# mainBoard.net
KiCad netlist of a schematic drawn in EAGLE
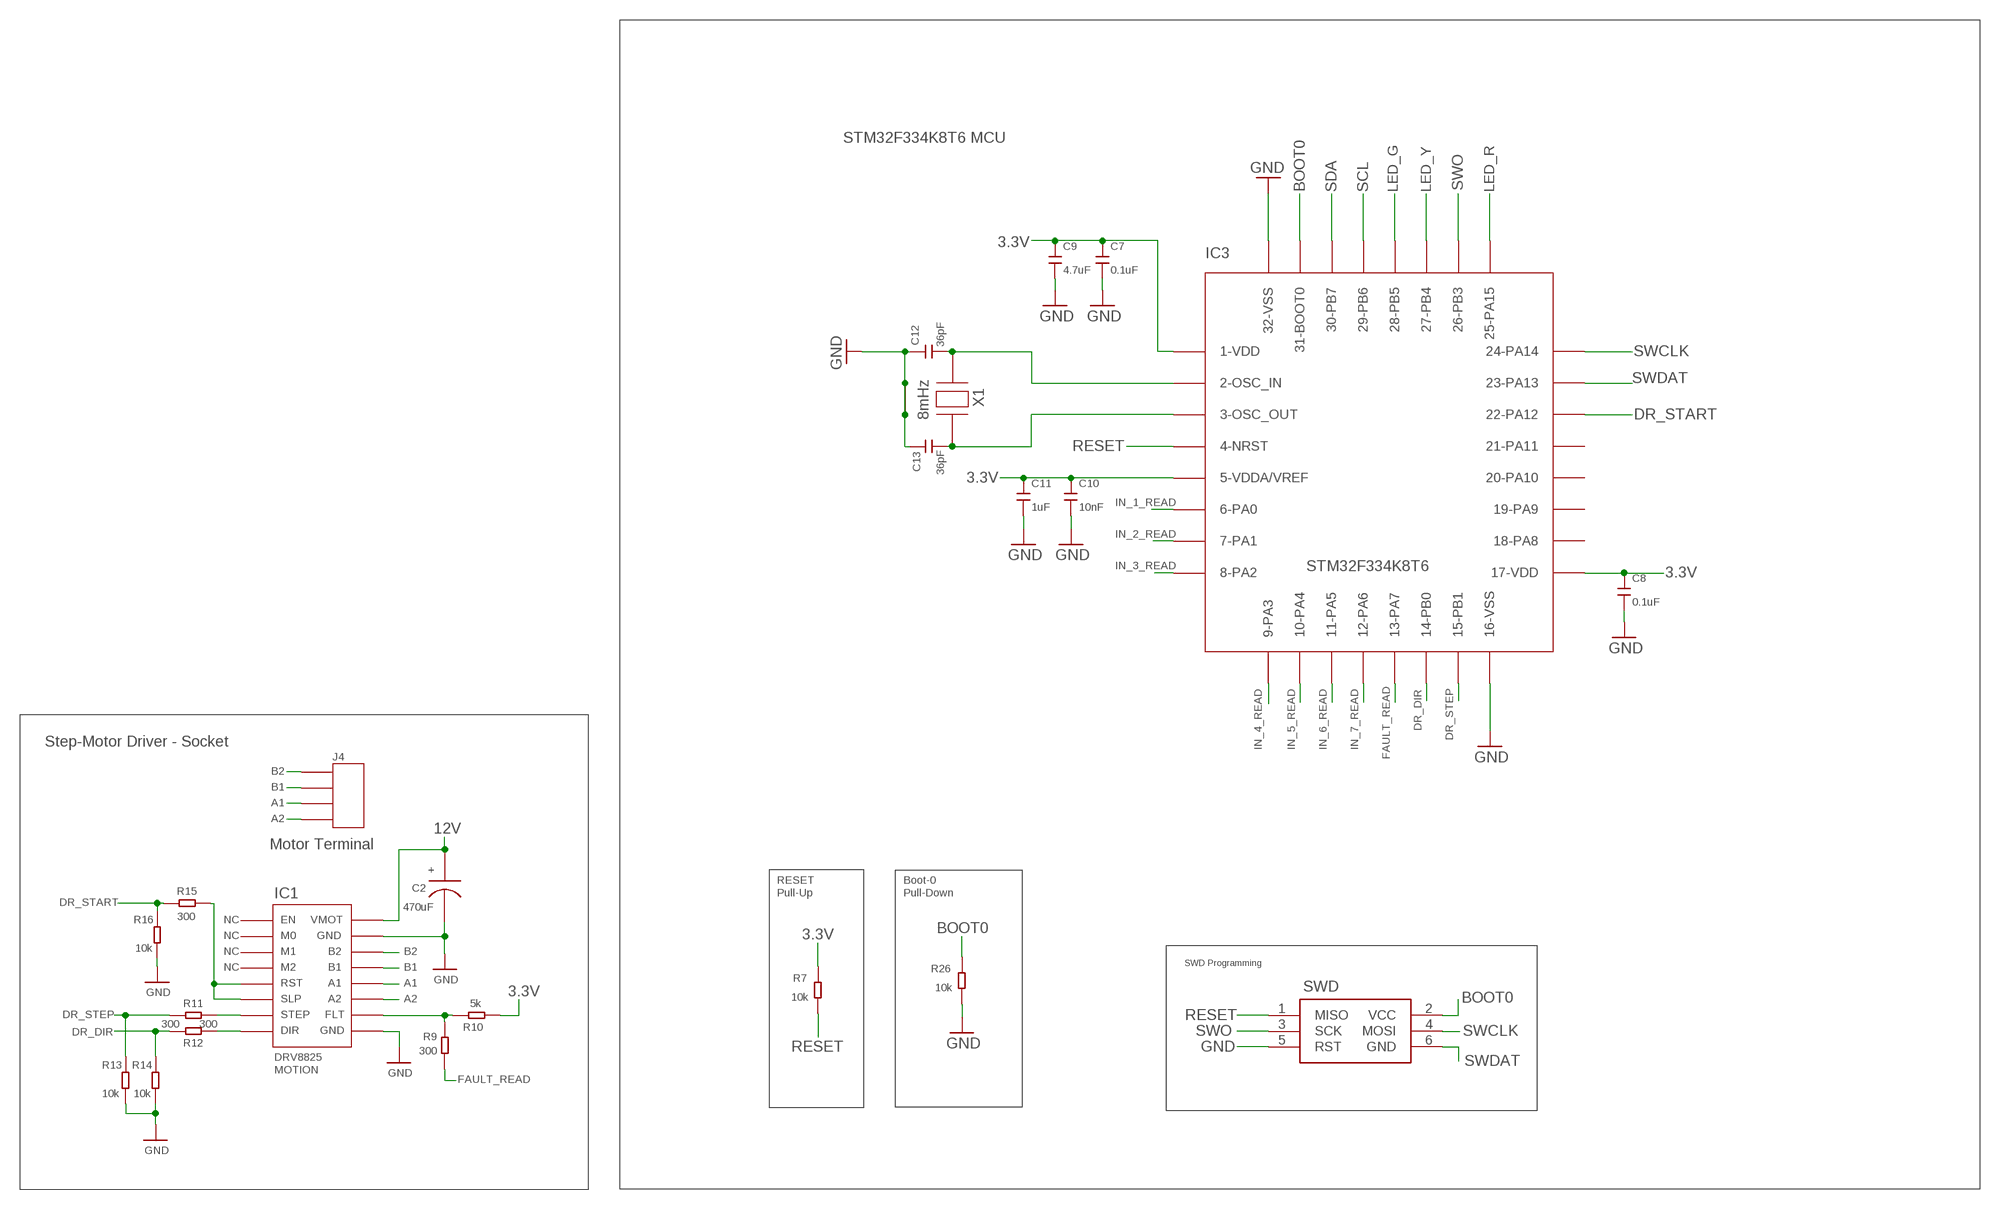
[diagram p0: schematic, sheet 1, part 1 of 2]
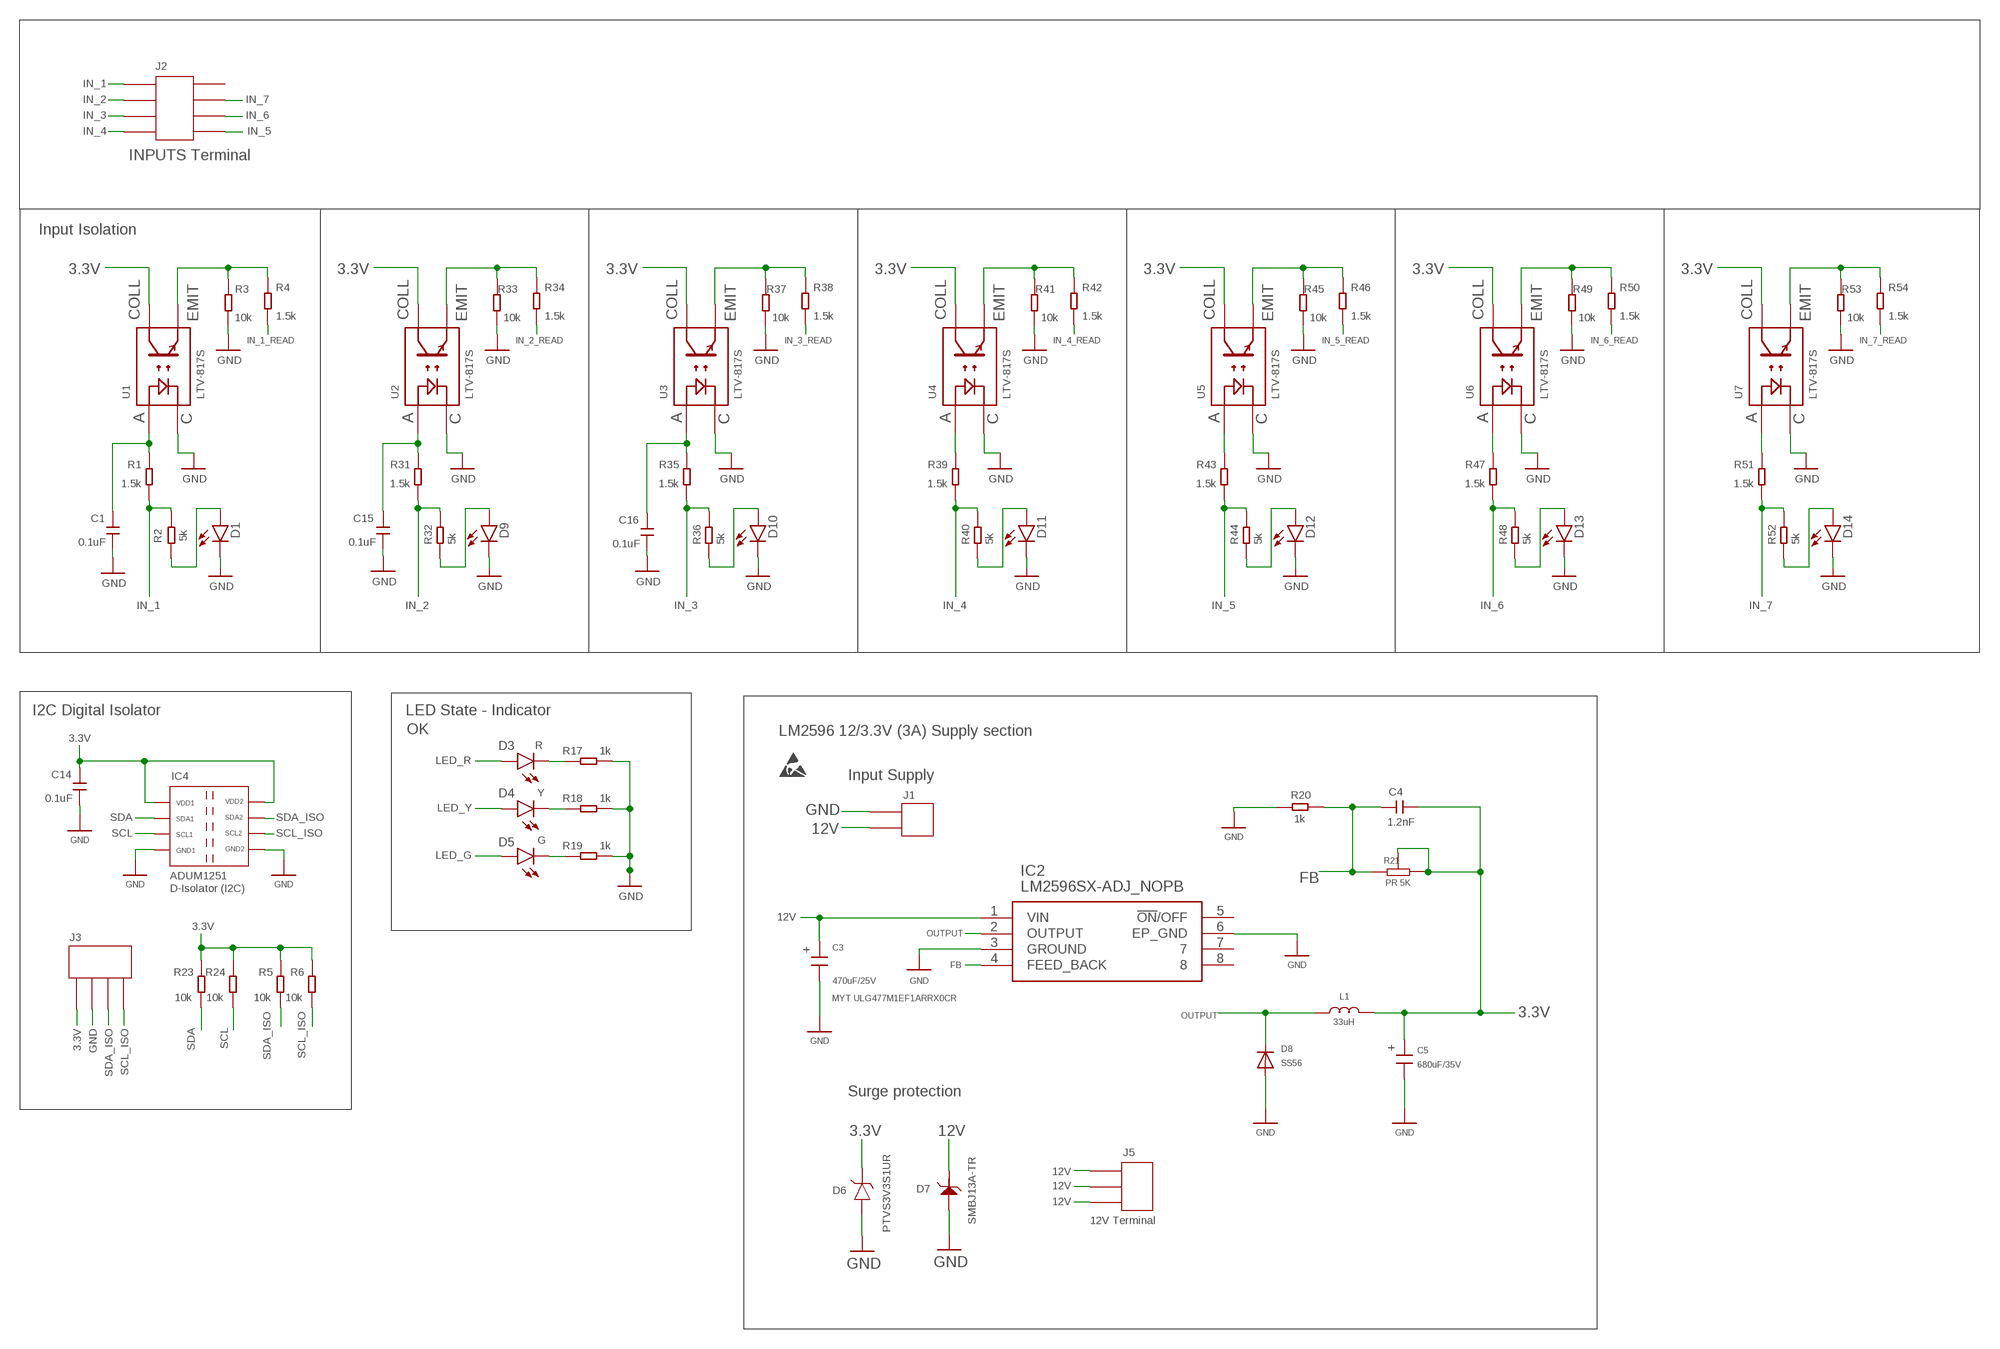
[diagram p1: schematic, sheet 1, part 2 of 2]

(export (version "E")
  (design (tool "Eeschema 10.0.6"))
  (components
    (comp (ref "C1")
      (value "0.1uF")
      (footprint "eagle-import:SMD-CAP-0805")
      (libsource (lib "eagle-import") (part "SMD-CAP-0805"))
    )
    (comp (ref "C2")
      (value "470uF")
      (footprint "eagle-import:EPCOS-CAP-10X16")
      (libsource (lib "eagle-import") (part "EPCOS-CAP-10X16"))
    )
    (comp (ref "C3")
      (value "MYT-680UF-25V-D8MM-F16")
      (footprint "eagle-import:MYT-680UF-25V-D8MM-F16")
      (libsource (lib "eagle-import") (part "MYT-680UF-25V-D8MM-F16"))
    )
    (comp (ref "C4")
      (value "1.2nF")
      (footprint "eagle-import:SMD-CAP-0805")
      (libsource (lib "eagle-import") (part "SMD-CAP-0805"))
    )
    (comp (ref "C5")
      (value "PANASONIC-SMT-CAP-680UF")
      (footprint "eagle-import:PANASONIC-SMT-CAP-680UF")
      (libsource (lib "eagle-import") (part "PANASONIC-SMT-CAP-680UF"))
    )
    (comp (ref "C7")
      (value "0.1uF")
      (footprint "eagle-import:SMD-CAP-0805")
      (libsource (lib "eagle-import") (part "SMD-CAP-0805"))
    )
    (comp (ref "C8")
      (value "0.1uF")
      (footprint "eagle-import:SMD-CAP-0805")
      (libsource (lib "eagle-import") (part "SMD-CAP-0805"))
    )
    (comp (ref "C9")
      (value "4.7uF")
      (footprint "eagle-import:SMD-CAP-0805")
      (libsource (lib "eagle-import") (part "SMD-CAP-0805"))
    )
    (comp (ref "C10")
      (value "10nF")
      (footprint "eagle-import:SMD-CAP-0805")
      (libsource (lib "eagle-import") (part "SMD-CAP-0805"))
    )
    (comp (ref "C11")
      (value "1uF")
      (footprint "eagle-import:SMD-CAP-0805")
      (libsource (lib "eagle-import") (part "SMD-CAP-0805"))
    )
    (comp (ref "C12")
      (value "36pF")
      (footprint "eagle-import:SMD-CAP-0603")
      (libsource (lib "eagle-import") (part "SMD-CAP-0603"))
    )
    (comp (ref "C13")
      (value "36pF")
      (footprint "eagle-import:SMD-CAP-0603")
      (libsource (lib "eagle-import") (part "SMD-CAP-0603"))
    )
    (comp (ref "C14")
      (value "0.1uF")
      (footprint "eagle-import:SMD-CAP-0805")
      (libsource (lib "eagle-import") (part "SMD-CAP-0805"))
    )
    (comp (ref "C15")
      (value "0.1uF")
      (footprint "eagle-import:SMD-CAP-0805")
      (libsource (lib "eagle-import") (part "SMD-CAP-0805"))
    )
    (comp (ref "C16")
      (value "0.1uF")
      (footprint "eagle-import:SMD-CAP-0805")
      (libsource (lib "eagle-import") (part "SMD-CAP-0805"))
    )
    (comp (ref "D1")
      (value "LED0603")
      (footprint "eagle-import:LED-0603")
      (libsource (lib "eagle-import") (part "LED0603"))
    )
    (comp (ref "D3")
      (value "R")
      (footprint "eagle-import:LED-0603")
      (libsource (lib "eagle-import") (part "LED0603"))
    )
    (comp (ref "D4")
      (value "Y")
      (footprint "eagle-import:LED-0603")
      (libsource (lib "eagle-import") (part "LED0603"))
    )
    (comp (ref "D5")
      (value "G")
      (footprint "eagle-import:LED-0603")
      (libsource (lib "eagle-import") (part "LED0603"))
    )
    (comp (ref "D6")
      (value "PTVS3V3S1UR")
      (footprint "eagle-import:PTVS3V3S1UR")
      (libsource (lib "eagle-import") (part "PTVS3V3S1UR"))
    )
    (comp (ref "D7")
      (value "TVS-SMBJ13A-LFUSE")
      (footprint "eagle-import:TVS-SMBJ13A-LFUSE")
      (libsource (lib "eagle-import") (part "TVS-SMBJ13A-LFUSE"))
    )
    (comp (ref "D8")
      (value "S2A")
      (footprint "eagle-import:DO214AA")
      (fields (field (name "MF") "Fairchild"))
      (libsource (lib "eagle-import") (part "S2A"))
    )
    (comp (ref "D9")
      (value "LED0603")
      (footprint "eagle-import:LED-0603")
      (libsource (lib "eagle-import") (part "LED0603"))
    )
    (comp (ref "D10")
      (value "LED0603")
      (footprint "eagle-import:LED-0603")
      (libsource (lib "eagle-import") (part "LED0603"))
    )
    (comp (ref "D11")
      (value "LED0603")
      (footprint "eagle-import:LED-0603")
      (libsource (lib "eagle-import") (part "LED0603"))
    )
    (comp (ref "D12")
      (value "LED0603")
      (footprint "eagle-import:LED-0603")
      (libsource (lib "eagle-import") (part "LED0603"))
    )
    (comp (ref "D13")
      (value "LED0603")
      (footprint "eagle-import:LED-0603")
      (libsource (lib "eagle-import") (part "LED0603"))
    )
    (comp (ref "D14")
      (value "LED0603")
      (footprint "eagle-import:LED-0603")
      (libsource (lib "eagle-import") (part "LED0603"))
    )
    (comp (ref "IC1")
      (value "DRV8825-DRIVER")
      (footprint "eagle-import:DRV8825-DRIVER")
      (libsource (lib "eagle-import") (part "DRV8825-DRIVER"))
    )
    (comp (ref "IC2")
      (value "LM2596SX-ADJ_NOPB")
      (footprint "eagle-import:LM2596SXADJNOPB")
      (fields
        (field (name "MANUFACTURER_PART_NUMBER") "LM2596SX-ADJ/NOPB")
        (field (name "MOUSER_PART_NUMBER") "926-LM2596SX-ADJNOPB")
      )
      (libsource (lib "eagle-import") (part "LM2596SX-ADJ_NOPB"))
    )
    (comp (ref "IC3")
      (value "STM32F334K8T6")
      (footprint "eagle-import:QFP80P900X900X160-32N")
      (libsource (lib "eagle-import") (part "STM32F334K8T6"))
    )
    (comp (ref "IC4")
      (value "ADUM1251ARZ-RL7")
      (footprint "eagle-import:ADUM1251ARZ-RL7")
      (libsource (lib "eagle-import") (part "ADUM1251ARZ-RL7"))
    )
    (comp (ref "J1")
      (value "DG127-5.0-2P")
      (footprint "eagle-import:DG127-5.0-2P")
      (libsource (lib "eagle-import") (part "DG127-5.0-2P"))
    )
    (comp (ref "J2")
      (value "5EHDR-08P-5.00")
      (footprint "eagle-import:5EHDR-08P-5.00")
      (libsource (lib "eagle-import") (part "5EHDR-08P-5.00"))
    )
    (comp (ref "J3")
      (value "DG127-5.0-4P")
      (footprint "eagle-import:DG127-5.0-4P")
      (libsource (lib "eagle-import") (part "DG127-5.0-4P"))
    )
    (comp (ref "J4")
      (value "DG127-5.0-4P")
      (footprint "eagle-import:DG127-5.0-4P")
      (libsource (lib "eagle-import") (part "DG127-5.0-4P"))
    )
    (comp (ref "J5")
      (value "PRESS-TERMINAL-5.0-3P")
      (footprint "eagle-import:PRESS-TERMINAL-5.0-3P")
      (libsource (lib "eagle-import") (part "PRESS-TERMINAL-5.0-3P"))
    )
    (comp (ref "L1")
      (value "SUNLTECHTEC-HSLO1365H330MTT")
      (footprint "eagle-import:SUNLTECHTEC-HSLO1365H330MTT")
      (libsource (lib "eagle-import") (part "SUNLTECHTEC-HSLO1365H330MTT"))
    )
    (comp (ref "R1")
      (value "1.5k")
      (footprint "eagle-import:R0805")
      (fields (field (name "MPN") "RL0805JR-070R1L"))
      (libsource (lib "eagle-import") (part "SMD-RES-0805"))
    )
    (comp (ref "R2")
      (value "5k")
      (footprint "eagle-import:SMD-RES-0603")
      (libsource (lib "eagle-import") (part "SMD-RES-0603"))
    )
    (comp (ref "R3")
      (value "10k")
      (footprint "eagle-import:R0805")
      (fields (field (name "MPN") "RL0805JR-070R1L"))
      (libsource (lib "eagle-import") (part "SMD-RES-0805"))
    )
    (comp (ref "R4")
      (value "1.5k")
      (footprint "eagle-import:R0805")
      (fields (field (name "MPN") "RL0805JR-070R1L"))
      (libsource (lib "eagle-import") (part "SMD-RES-0805"))
    )
    (comp (ref "R5")
      (value "10k")
      (footprint "eagle-import:R0805")
      (fields (field (name "MPN") "RL0805JR-070R1L"))
      (libsource (lib "eagle-import") (part "SMD-RES-0805"))
    )
    (comp (ref "R6")
      (value "10k")
      (footprint "eagle-import:R0805")
      (fields (field (name "MPN") "RL0805JR-070R1L"))
      (libsource (lib "eagle-import") (part "SMD-RES-0805"))
    )
    (comp (ref "R7")
      (value "10k")
      (footprint "eagle-import:SMD-RES-0603")
      (libsource (lib "eagle-import") (part "SMD-RES-0603"))
    )
    (comp (ref "R9")
      (value "300")
      (footprint "eagle-import:R0805")
      (fields (field (name "MPN") "RL0805JR-070R1L"))
      (libsource (lib "eagle-import") (part "SMD-RES-0805"))
    )
    (comp (ref "R10")
      (value "5k")
      (footprint "eagle-import:R0805")
      (fields (field (name "MPN") "RL0805JR-070R1L"))
      (libsource (lib "eagle-import") (part "SMD-RES-0805"))
    )
    (comp (ref "R11")
      (value "300")
      (footprint "eagle-import:R0805")
      (fields (field (name "MPN") "RL0805JR-070R1L"))
      (libsource (lib "eagle-import") (part "SMD-RES-0805"))
    )
    (comp (ref "R12")
      (value "300")
      (footprint "eagle-import:R0805")
      (fields (field (name "MPN") "RL0805JR-070R1L"))
      (libsource (lib "eagle-import") (part "SMD-RES-0805"))
    )
    (comp (ref "R13")
      (value "10k")
      (footprint "eagle-import:R0805")
      (fields (field (name "MPN") "RL0805JR-070R1L"))
      (libsource (lib "eagle-import") (part "SMD-RES-0805"))
    )
    (comp (ref "R14")
      (value "10k")
      (footprint "eagle-import:R0805")
      (fields (field (name "MPN") "RL0805JR-070R1L"))
      (libsource (lib "eagle-import") (part "SMD-RES-0805"))
    )
    (comp (ref "R15")
      (value "300")
      (footprint "eagle-import:R0805")
      (fields (field (name "MPN") "RL0805JR-070R1L"))
      (libsource (lib "eagle-import") (part "SMD-RES-0805"))
    )
    (comp (ref "R16")
      (value "10k")
      (footprint "eagle-import:R0805")
      (fields (field (name "MPN") "RL0805JR-070R1L"))
      (libsource (lib "eagle-import") (part "SMD-RES-0805"))
    )
    (comp (ref "R17")
      (value "1k")
      (footprint "eagle-import:SMD-RES-0603")
      (libsource (lib "eagle-import") (part "SMD-RES-0603"))
    )
    (comp (ref "R18")
      (value "1k")
      (footprint "eagle-import:SMD-RES-0603")
      (libsource (lib "eagle-import") (part "SMD-RES-0603"))
    )
    (comp (ref "R19")
      (value "1k")
      (footprint "eagle-import:SMD-RES-0603")
      (libsource (lib "eagle-import") (part "SMD-RES-0603"))
    )
    (comp (ref "R20")
      (value "1k")
      (footprint "eagle-import:R0805")
      (fields (field (name "MPN") "RL0805JR-070R1L"))
      (libsource (lib "eagle-import") (part "SMD-RES-0805"))
    )
    (comp (ref "R21")
      (value "BOURNS-3296W-PREC-RESISTOR-5K")
      (footprint "eagle-import:BOURNS-3296W-PREC-RESISTOR-5K")
      (libsource (lib "eagle-import") (part "BOURNS-3296W-PREC-RESISTOR-5K"))
    )
    (comp (ref "R23")
      (value "10k")
      (footprint "eagle-import:R0805")
      (fields (field (name "MPN") "RL0805JR-070R1L"))
      (libsource (lib "eagle-import") (part "SMD-RES-0805"))
    )
    (comp (ref "R24")
      (value "10k")
      (footprint "eagle-import:R0805")
      (fields (field (name "MPN") "RL0805JR-070R1L"))
      (libsource (lib "eagle-import") (part "SMD-RES-0805"))
    )
    (comp (ref "R26")
      (value "10k")
      (footprint "eagle-import:SMD-RES-0603")
      (libsource (lib "eagle-import") (part "SMD-RES-0603"))
    )
    (comp (ref "R31")
      (value "1.5k")
      (footprint "eagle-import:R0805")
      (fields (field (name "MPN") "RL0805JR-070R1L"))
      (libsource (lib "eagle-import") (part "SMD-RES-0805"))
    )
    (comp (ref "R32")
      (value "5k")
      (footprint "eagle-import:SMD-RES-0603")
      (libsource (lib "eagle-import") (part "SMD-RES-0603"))
    )
    (comp (ref "R33")
      (value "10k")
      (footprint "eagle-import:R0805")
      (fields (field (name "MPN") "RL0805JR-070R1L"))
      (libsource (lib "eagle-import") (part "SMD-RES-0805"))
    )
    (comp (ref "R34")
      (value "1.5k")
      (footprint "eagle-import:R0805")
      (fields (field (name "MPN") "RL0805JR-070R1L"))
      (libsource (lib "eagle-import") (part "SMD-RES-0805"))
    )
    (comp (ref "R35")
      (value "1.5k")
      (footprint "eagle-import:R0805")
      (fields (field (name "MPN") "RL0805JR-070R1L"))
      (libsource (lib "eagle-import") (part "SMD-RES-0805"))
    )
    (comp (ref "R36")
      (value "5k")
      (footprint "eagle-import:SMD-RES-0603")
      (libsource (lib "eagle-import") (part "SMD-RES-0603"))
    )
    (comp (ref "R37")
      (value "10k")
      (footprint "eagle-import:R0805")
      (fields (field (name "MPN") "RL0805JR-070R1L"))
      (libsource (lib "eagle-import") (part "SMD-RES-0805"))
    )
    (comp (ref "R38")
      (value "1.5k")
      (footprint "eagle-import:R0805")
      (fields (field (name "MPN") "RL0805JR-070R1L"))
      (libsource (lib "eagle-import") (part "SMD-RES-0805"))
    )
    (comp (ref "R39")
      (value "1.5k")
      (footprint "eagle-import:R0805")
      (fields (field (name "MPN") "RL0805JR-070R1L"))
      (libsource (lib "eagle-import") (part "SMD-RES-0805"))
    )
    (comp (ref "R40")
      (value "5k")
      (footprint "eagle-import:SMD-RES-0603")
      (libsource (lib "eagle-import") (part "SMD-RES-0603"))
    )
    (comp (ref "R41")
      (value "10k")
      (footprint "eagle-import:R0805")
      (fields (field (name "MPN") "RL0805JR-070R1L"))
      (libsource (lib "eagle-import") (part "SMD-RES-0805"))
    )
    (comp (ref "R42")
      (value "1.5k")
      (footprint "eagle-import:R0805")
      (fields (field (name "MPN") "RL0805JR-070R1L"))
      (libsource (lib "eagle-import") (part "SMD-RES-0805"))
    )
    (comp (ref "R43")
      (value "1.5k")
      (footprint "eagle-import:R0805")
      (fields (field (name "MPN") "RL0805JR-070R1L"))
      (libsource (lib "eagle-import") (part "SMD-RES-0805"))
    )
    (comp (ref "R44")
      (value "5k")
      (footprint "eagle-import:SMD-RES-0603")
      (libsource (lib "eagle-import") (part "SMD-RES-0603"))
    )
    (comp (ref "R45")
      (value "10k")
      (footprint "eagle-import:R0805")
      (fields (field (name "MPN") "RL0805JR-070R1L"))
      (libsource (lib "eagle-import") (part "SMD-RES-0805"))
    )
    (comp (ref "R46")
      (value "1.5k")
      (footprint "eagle-import:R0805")
      (fields (field (name "MPN") "RL0805JR-070R1L"))
      (libsource (lib "eagle-import") (part "SMD-RES-0805"))
    )
    (comp (ref "R47")
      (value "1.5k")
      (footprint "eagle-import:R0805")
      (fields (field (name "MPN") "RL0805JR-070R1L"))
      (libsource (lib "eagle-import") (part "SMD-RES-0805"))
    )
    (comp (ref "R48")
      (value "5k")
      (footprint "eagle-import:SMD-RES-0603")
      (libsource (lib "eagle-import") (part "SMD-RES-0603"))
    )
    (comp (ref "R49")
      (value "10k")
      (footprint "eagle-import:R0805")
      (fields (field (name "MPN") "RL0805JR-070R1L"))
      (libsource (lib "eagle-import") (part "SMD-RES-0805"))
    )
    (comp (ref "R50")
      (value "1.5k")
      (footprint "eagle-import:R0805")
      (fields (field (name "MPN") "RL0805JR-070R1L"))
      (libsource (lib "eagle-import") (part "SMD-RES-0805"))
    )
    (comp (ref "R51")
      (value "1.5k")
      (footprint "eagle-import:R0805")
      (fields (field (name "MPN") "RL0805JR-070R1L"))
      (libsource (lib "eagle-import") (part "SMD-RES-0805"))
    )
    (comp (ref "R52")
      (value "5k")
      (footprint "eagle-import:SMD-RES-0603")
      (libsource (lib "eagle-import") (part "SMD-RES-0603"))
    )
    (comp (ref "R53")
      (value "10k")
      (footprint "eagle-import:R0805")
      (fields (field (name "MPN") "RL0805JR-070R1L"))
      (libsource (lib "eagle-import") (part "SMD-RES-0805"))
    )
    (comp (ref "R54")
      (value "1.5k")
      (footprint "eagle-import:R0805")
      (fields (field (name "MPN") "RL0805JR-070R1L"))
      (libsource (lib "eagle-import") (part "SMD-RES-0805"))
    )
    (comp (ref "SWD")
      (value "AVRISP-6")
      (footprint "eagle-import:AVRISP")
      (libsource (lib "eagle-import") (part "AVRISP-6"))
    )
    (comp (ref "U$1")
      (value "ESD-LOGO")
      (footprint "eagle-import:ESD-LOGO")
      (libsource (lib "eagle-import") (part "ESD-LOGO"))
    )
    (comp (ref "U1")
      (value "LTV-817S")
      (footprint "eagle-import:LTV-817S")
      (libsource (lib "eagle-import") (part "LTV-817S"))
    )
    (comp (ref "U2")
      (value "LTV-817S")
      (footprint "eagle-import:LTV-817S")
      (libsource (lib "eagle-import") (part "LTV-817S"))
    )
    (comp (ref "U3")
      (value "LTV-817S")
      (footprint "eagle-import:LTV-817S")
      (libsource (lib "eagle-import") (part "LTV-817S"))
    )
    (comp (ref "U4")
      (value "LTV-817S")
      (footprint "eagle-import:LTV-817S")
      (libsource (lib "eagle-import") (part "LTV-817S"))
    )
    (comp (ref "U5")
      (value "LTV-817S")
      (footprint "eagle-import:LTV-817S")
      (libsource (lib "eagle-import") (part "LTV-817S"))
    )
    (comp (ref "U6")
      (value "LTV-817S")
      (footprint "eagle-import:LTV-817S")
      (libsource (lib "eagle-import") (part "LTV-817S"))
    )
    (comp (ref "U7")
      (value "LTV-817S")
      (footprint "eagle-import:LTV-817S")
      (libsource (lib "eagle-import") (part "LTV-817S"))
    )
    (comp (ref "X1")
      (value "8mHz")
      (footprint "eagle-import:CRYSTALL-YTC-X50328MSB4SI")
      (libsource (lib "eagle-import") (part "CRYSTALL-YTC-X50328MSB4SI"))
    )
  )
  (nets
    (net (code "1") (name "/3.3V") (class "Default")
      (node (ref "C10") (pin "2") (pinfunction "2_2") (pintype "passive"))
      (node (ref "C11") (pin "2") (pinfunction "2_2") (pintype "passive"))
      (node (ref "C14") (pin "2") (pinfunction "2_2") (pintype "passive"))
      (node (ref "C4") (pin "2") (pinfunction "2_2") (pintype "passive"))
      (node (ref "C5") (pin "+") (pinfunction "+_+") (pintype "bidirectional"))
      (node (ref "C7") (pin "2") (pinfunction "2_2") (pintype "passive"))
      (node (ref "C8") (pin "2") (pinfunction "2_2") (pintype "passive"))
      (node (ref "C9") (pin "2") (pinfunction "2_2") (pintype "passive"))
      (node (ref "D6") (pin "C") (pinfunction "C_C") (pintype "bidirectional"))
      (node (ref "IC3") (pin "1-VDD") (pinfunction "1-VDD_1-VDD") (pintype "bidirectional"))
      (node (ref "IC3") (pin "17-VDD") (pinfunction "17-VDD_17-VDD") (pintype "bidirectional"))
      (node (ref "IC3") (pin "5-VDDA/VREF") (pinfunction "5-VDDA/VREF_5-VDDA/VREF") (pintype "bidirectional"))
      (node (ref "IC4") (pin "VDD1") (pinfunction "VDD1_VDD1") (pintype "bidirectional"))
      (node (ref "IC4") (pin "VDD2") (pinfunction "VDD2_VDD2") (pintype "bidirectional"))
      (node (ref "J3") (pin "P$1") (pinfunction "P$1_P$1") (pintype "bidirectional"))
      (node (ref "L1") (pin "P$2") (pinfunction "P$2_P$2") (pintype "bidirectional"))
      (node (ref "R10") (pin "2") (pinfunction "2_2") (pintype "passive"))
      (node (ref "R21") (pin "CW-3") (pinfunction "CW-3_CW-3") (pintype "bidirectional"))
      (node (ref "R21") (pin "WIPER-2") (pinfunction "WIPER-2_WIPER-2") (pintype "bidirectional"))
      (node (ref "R23") (pin "2") (pinfunction "2_2") (pintype "passive"))
      (node (ref "R24") (pin "2") (pinfunction "2_2") (pintype "passive"))
      (node (ref "R5") (pin "2") (pinfunction "2_2") (pintype "passive"))
      (node (ref "R6") (pin "2") (pinfunction "2_2") (pintype "passive"))
      (node (ref "R7") (pin "2") (pinfunction "2_2") (pintype "passive"))
      (node (ref "U1") (pin "COLL") (pinfunction "COLLECTOR_COLL") (pintype "bidirectional"))
      (node (ref "U2") (pin "COLL") (pinfunction "COLLECTOR_COLL") (pintype "bidirectional"))
      (node (ref "U3") (pin "COLL") (pinfunction "COLLECTOR_COLL") (pintype "bidirectional"))
      (node (ref "U4") (pin "COLL") (pinfunction "COLLECTOR_COLL") (pintype "bidirectional"))
      (node (ref "U5") (pin "COLL") (pinfunction "COLLECTOR_COLL") (pintype "bidirectional"))
      (node (ref "U6") (pin "COLL") (pinfunction "COLLECTOR_COLL") (pintype "bidirectional"))
      (node (ref "U7") (pin "COLL") (pinfunction "COLLECTOR_COLL") (pintype "bidirectional"))
    )
    (net (code "2") (name "/12V") (class "Default")
      (node (ref "C2") (pin "+") (pinfunction "+_+") (pintype "bidirectional"))
      (node (ref "C3") (pin "+") (pinfunction "+_+") (pintype "bidirectional"))
      (node (ref "D7") (pin "-") (pinfunction "-_-") (pintype "bidirectional"))
      (node (ref "IC1") (pin "VMOT") (pinfunction "VMOT_VMOT") (pintype "bidirectional"))
      (node (ref "IC2") (pin "1") (pinfunction "VIN_1") (pintype "bidirectional"))
      (node (ref "J1") (pin "P$2") (pinfunction "P$2_P$2") (pintype "bidirectional"))
      (node (ref "J5") (pin "A1") (pinfunction "P$1_A1") (pintype "bidirectional"))
      (node (ref "J5") (pin "A2") (pinfunction "P$2_A2") (pintype "bidirectional"))
      (node (ref "J5") (pin "A3") (pinfunction "P$3_A3") (pintype "bidirectional"))
      (node (ref "J5") (pin "B1") (pinfunction "P$1_B1") (pintype "bidirectional"))
      (node (ref "J5") (pin "B2") (pinfunction "P$2_B2") (pintype "bidirectional"))
      (node (ref "J5") (pin "B3") (pinfunction "P$3_B3") (pintype "bidirectional"))
    )
    (net (code "3") (name "/A1") (class "Default")
      (node (ref "IC1") (pin "A1") (pinfunction "A1_A1") (pintype "bidirectional"))
      (node (ref "J4") (pin "P$3") (pinfunction "P$3_P$3") (pintype "bidirectional"))
    )
    (net (code "4") (name "/A2") (class "Default")
      (node (ref "IC1") (pin "A2") (pinfunction "A2_A2") (pintype "bidirectional"))
      (node (ref "J4") (pin "P$4") (pinfunction "P$4_P$4") (pintype "bidirectional"))
    )
    (net (code "5") (name "/B1") (class "Default")
      (node (ref "IC1") (pin "B1") (pinfunction "B1_B1") (pintype "bidirectional"))
      (node (ref "J4") (pin "P$2") (pinfunction "P$2_P$2") (pintype "bidirectional"))
    )
    (net (code "6") (name "/B2") (class "Default")
      (node (ref "IC1") (pin "B2") (pinfunction "B2_B2") (pintype "bidirectional"))
      (node (ref "J4") (pin "P$1") (pinfunction "P$1_P$1") (pintype "bidirectional"))
    )
    (net (code "7") (name "/BOOT0") (class "Default")
      (node (ref "IC3") (pin "31-BOOT0") (pinfunction "31-BOOT0_31-BOOT0") (pintype "bidirectional"))
      (node (ref "R26") (pin "2") (pinfunction "2_2") (pintype "passive"))
      (node (ref "SWD") (pin "2") (pinfunction "VCC_2") (pintype "power_in"))
    )
    (net (code "8") (name "/DR_DIR") (class "Default")
      (node (ref "IC3") (pin "14-PB0") (pinfunction "14-PB0_14-PB0") (pintype "bidirectional"))
      (node (ref "R12") (pin "1") (pinfunction "1_1") (pintype "passive"))
      (node (ref "R14") (pin "2") (pinfunction "2_2") (pintype "passive"))
    )
    (net (code "9") (name "/DR_START") (class "Default")
      (node (ref "IC3") (pin "22-PA12") (pinfunction "22-PA12_22-PA12") (pintype "bidirectional"))
      (node (ref "R15") (pin "1") (pinfunction "1_1") (pintype "passive"))
      (node (ref "R16") (pin "2") (pinfunction "2_2") (pintype "passive"))
    )
    (net (code "10") (name "/DR_STEP") (class "Default")
      (node (ref "IC3") (pin "15-PB1") (pinfunction "15-PB1_15-PB1") (pintype "bidirectional"))
      (node (ref "R11") (pin "1") (pinfunction "1_1") (pintype "passive"))
      (node (ref "R13") (pin "2") (pinfunction "2_2") (pintype "passive"))
    )
    (net (code "11") (name "/FAULT_READ") (class "Default")
      (node (ref "IC3") (pin "13-PA7") (pinfunction "13-PA7_13-PA7") (pintype "bidirectional"))
      (node (ref "R9") (pin "2") (pinfunction "2_2") (pintype "passive"))
    )
    (net (code "12") (name "/FB") (class "Default")
      (node (ref "C4") (pin "1") (pinfunction "1_1") (pintype "passive"))
      (node (ref "IC2") (pin "4") (pinfunction "FEED_BACK_4") (pintype "bidirectional"))
      (node (ref "R20") (pin "2") (pinfunction "2_2") (pintype "passive"))
      (node (ref "R21") (pin "CCW-1") (pinfunction "CCW-1_CCW-1") (pintype "bidirectional"))
    )
    (net (code "13") (name "/IN_1") (class "Default")
      (node (ref "J2") (pin "1") (pinfunction "1_1") (pintype "bidirectional"))
      (node (ref "R1") (pin "1") (pinfunction "1_1") (pintype "passive"))
      (node (ref "R2") (pin "2") (pinfunction "2_2") (pintype "passive"))
    )
    (net (code "14") (name "/IN_1_READ") (class "Default")
      (node (ref "IC3") (pin "6-PA0") (pinfunction "6-PA0_6-PA0") (pintype "bidirectional"))
      (node (ref "R4") (pin "2") (pinfunction "2_2") (pintype "passive"))
    )
    (net (code "15") (name "/IN_2") (class "Default")
      (node (ref "J2") (pin "2") (pinfunction "2_2") (pintype "bidirectional"))
      (node (ref "R31") (pin "1") (pinfunction "1_1") (pintype "passive"))
      (node (ref "R32") (pin "2") (pinfunction "2_2") (pintype "passive"))
    )
    (net (code "16") (name "/IN_2_READ") (class "Default")
      (node (ref "IC3") (pin "7-PA1") (pinfunction "7-PA1_7-PA1") (pintype "bidirectional"))
      (node (ref "R34") (pin "2") (pinfunction "2_2") (pintype "passive"))
    )
    (net (code "17") (name "/IN_3") (class "Default")
      (node (ref "J2") (pin "3") (pinfunction "3_3") (pintype "bidirectional"))
      (node (ref "R35") (pin "1") (pinfunction "1_1") (pintype "passive"))
      (node (ref "R36") (pin "2") (pinfunction "2_2") (pintype "passive"))
    )
    (net (code "18") (name "/IN_3_READ") (class "Default")
      (node (ref "IC3") (pin "8-PA2") (pinfunction "8-PA2_8-PA2") (pintype "bidirectional"))
      (node (ref "R38") (pin "2") (pinfunction "2_2") (pintype "passive"))
    )
    (net (code "19") (name "/IN_4") (class "Default")
      (node (ref "J2") (pin "4") (pinfunction "4_4") (pintype "bidirectional"))
      (node (ref "R39") (pin "1") (pinfunction "1_1") (pintype "passive"))
      (node (ref "R40") (pin "2") (pinfunction "2_2") (pintype "passive"))
    )
    (net (code "20") (name "/IN_4_READ") (class "Default")
      (node (ref "IC3") (pin "9-PA3") (pinfunction "9-PA3_9-PA3") (pintype "bidirectional"))
      (node (ref "R42") (pin "2") (pinfunction "2_2") (pintype "passive"))
    )
    (net (code "21") (name "/IN_5") (class "Default")
      (node (ref "J2") (pin "5") (pinfunction "5_5") (pintype "bidirectional"))
      (node (ref "R43") (pin "1") (pinfunction "1_1") (pintype "passive"))
      (node (ref "R44") (pin "2") (pinfunction "2_2") (pintype "passive"))
    )
    (net (code "22") (name "/IN_5_READ") (class "Default")
      (node (ref "IC3") (pin "10-PA4") (pinfunction "10-PA4_10-PA4") (pintype "bidirectional"))
      (node (ref "R46") (pin "2") (pinfunction "2_2") (pintype "passive"))
    )
    (net (code "23") (name "/IN_6") (class "Default")
      (node (ref "J2") (pin "6") (pinfunction "6_6") (pintype "bidirectional"))
      (node (ref "R47") (pin "1") (pinfunction "1_1") (pintype "passive"))
      (node (ref "R48") (pin "2") (pinfunction "2_2") (pintype "passive"))
    )
    (net (code "24") (name "/IN_6_READ") (class "Default")
      (node (ref "IC3") (pin "11-PA5") (pinfunction "11-PA5_11-PA5") (pintype "bidirectional"))
      (node (ref "R50") (pin "2") (pinfunction "2_2") (pintype "passive"))
    )
    (net (code "25") (name "/IN_7") (class "Default")
      (node (ref "J2") (pin "7") (pinfunction "7_7") (pintype "bidirectional"))
      (node (ref "R51") (pin "1") (pinfunction "1_1") (pintype "passive"))
      (node (ref "R52") (pin "2") (pinfunction "2_2") (pintype "passive"))
    )
    (net (code "26") (name "/IN_7_READ") (class "Default")
      (node (ref "IC3") (pin "12-PA6") (pinfunction "12-PA6_12-PA6") (pintype "bidirectional"))
      (node (ref "R54") (pin "2") (pinfunction "2_2") (pintype "passive"))
    )
    (net (code "27") (name "/LED_G") (class "Default")
      (node (ref "D5") (pin "A") (pinfunction "A_A") (pintype "passive"))
      (node (ref "IC3") (pin "28-PB5") (pinfunction "28-PB5_28-PB5") (pintype "bidirectional"))
    )
    (net (code "28") (name "/LED_R") (class "Default")
      (node (ref "D3") (pin "A") (pinfunction "A_A") (pintype "passive"))
      (node (ref "IC3") (pin "25-PA15") (pinfunction "25-PA15_25-PA15") (pintype "bidirectional"))
    )
    (net (code "29") (name "/LED_Y") (class "Default")
      (node (ref "D4") (pin "A") (pinfunction "A_A") (pintype "passive"))
      (node (ref "IC3") (pin "27-PB4") (pinfunction "27-PB4_27-PB4") (pintype "bidirectional"))
    )
    (net (code "30") (name "/OUTPUT") (class "Default")
      (node (ref "D8") (pin "C") (pinfunction "C_C") (pintype "passive"))
      (node (ref "IC2") (pin "2") (pinfunction "OUTPUT_2") (pintype "bidirectional"))
      (node (ref "L1") (pin "P$1") (pinfunction "P$1_P$1") (pintype "bidirectional"))
    )
    (net (code "31") (name "/RESET") (class "Default")
      (node (ref "IC3") (pin "4-NRST") (pinfunction "4-NRST_4-NRST") (pintype "bidirectional"))
      (node (ref "R7") (pin "1") (pinfunction "1_1") (pintype "passive"))
      (node (ref "SWD") (pin "1") (pinfunction "MISO_1") (pintype "input"))
    )
    (net (code "32") (name "/SCL") (class "Default")
      (node (ref "IC3") (pin "29-PB6") (pinfunction "29-PB6_29-PB6") (pintype "bidirectional"))
      (node (ref "IC4") (pin "SCL1") (pinfunction "SCL1_SCL1") (pintype "bidirectional"))
      (node (ref "R24") (pin "1") (pinfunction "1_1") (pintype "passive"))
    )
    (net (code "33") (name "/SCL_ISO") (class "Default")
      (node (ref "IC4") (pin "SCL2") (pinfunction "SCL2_SCL2") (pintype "bidirectional"))
      (node (ref "J3") (pin "P$4") (pinfunction "P$4_P$4") (pintype "bidirectional"))
      (node (ref "R6") (pin "1") (pinfunction "1_1") (pintype "passive"))
    )
    (net (code "34") (name "/SDA") (class "Default")
      (node (ref "IC3") (pin "30-PB7") (pinfunction "30-PB7_30-PB7") (pintype "bidirectional"))
      (node (ref "IC4") (pin "SDA1") (pinfunction "SDA1_SDA1") (pintype "bidirectional"))
      (node (ref "R23") (pin "1") (pinfunction "1_1") (pintype "passive"))
    )
    (net (code "35") (name "/SDA_ISO") (class "Default")
      (node (ref "IC4") (pin "SDA2") (pinfunction "SDA2_SDA2") (pintype "bidirectional"))
      (node (ref "J3") (pin "P$3") (pinfunction "P$3_P$3") (pintype "bidirectional"))
      (node (ref "R5") (pin "1") (pinfunction "1_1") (pintype "passive"))
    )
    (net (code "36") (name "/SWCLK") (class "Default")
      (node (ref "IC3") (pin "24-PA14") (pinfunction "24-PA14_24-PA14") (pintype "bidirectional"))
      (node (ref "SWD") (pin "4") (pinfunction "MOSI_4") (pintype "output"))
    )
    (net (code "37") (name "/SWDAT") (class "Default")
      (node (ref "IC3") (pin "23-PA13") (pinfunction "23-PA13_23-PA13") (pintype "bidirectional"))
      (node (ref "SWD") (pin "6") (pinfunction "GND_6") (pintype "power_in"))
    )
    (net (code "38") (name "/SWO") (class "Default")
      (node (ref "IC3") (pin "26-PB3") (pinfunction "26-PB3_26-PB3") (pintype "bidirectional"))
      (node (ref "SWD") (pin "3") (pinfunction "SCK_3") (pintype "output"))
    )
    (net (code "39") (name "GND") (class "Default")
      (node (ref "C1") (pin "1") (pinfunction "1_1") (pintype "passive"))
      (node (ref "C10") (pin "1") (pinfunction "1_1") (pintype "passive"))
      (node (ref "C11") (pin "1") (pinfunction "1_1") (pintype "passive"))
      (node (ref "C12") (pin "1") (pinfunction "1_1") (pintype "passive"))
      (node (ref "C13") (pin "1") (pinfunction "1_1") (pintype "passive"))
      (node (ref "C14") (pin "1") (pinfunction "1_1") (pintype "passive"))
      (node (ref "C15") (pin "1") (pinfunction "1_1") (pintype "passive"))
      (node (ref "C16") (pin "1") (pinfunction "1_1") (pintype "passive"))
      (node (ref "C2") (pin "-") (pinfunction "-_-") (pintype "bidirectional"))
      (node (ref "C3") (pin "-") (pinfunction "-_-") (pintype "bidirectional"))
      (node (ref "C5") (pin "-") (pinfunction "-_-") (pintype "bidirectional"))
      (node (ref "C7") (pin "1") (pinfunction "1_1") (pintype "passive"))
      (node (ref "C8") (pin "1") (pinfunction "1_1") (pintype "passive"))
      (node (ref "C9") (pin "1") (pinfunction "1_1") (pintype "passive"))
      (node (ref "D1") (pin "C") (pinfunction "C_C") (pintype "passive"))
      (node (ref "D10") (pin "C") (pinfunction "C_C") (pintype "passive"))
      (node (ref "D11") (pin "C") (pinfunction "C_C") (pintype "passive"))
      (node (ref "D12") (pin "C") (pinfunction "C_C") (pintype "passive"))
      (node (ref "D13") (pin "C") (pinfunction "C_C") (pintype "passive"))
      (node (ref "D14") (pin "C") (pinfunction "C_C") (pintype "passive"))
      (node (ref "D6") (pin "A") (pinfunction "A_A") (pintype "bidirectional"))
      (node (ref "D7") (pin "+") (pinfunction "+_+") (pintype "bidirectional"))
      (node (ref "D8") (pin "A") (pinfunction "A_A") (pintype "passive"))
      (node (ref "D9") (pin "C") (pinfunction "C_C") (pintype "passive"))
      (node (ref "IC1") (pin "GND") (pinfunction "GND_GND") (pintype "bidirectional"))
      (node (ref "IC1") (pin "GND_1") (pinfunction "GND_1_GND_1") (pintype "bidirectional"))
      (node (ref "IC2") (pin "3") (pinfunction "GROUND_3") (pintype "bidirectional"))
      (node (ref "IC2") (pin "6") (pinfunction "EP_GND_6") (pintype "bidirectional"))
      (node (ref "IC3") (pin "16-VSS") (pinfunction "16-VSS_16-VSS") (pintype "bidirectional"))
      (node (ref "IC3") (pin "32-VSS") (pinfunction "32-VSS_32-VSS") (pintype "bidirectional"))
      (node (ref "IC4") (pin "GND1") (pinfunction "GND1_GND1") (pintype "bidirectional"))
      (node (ref "IC4") (pin "GND2") (pinfunction "GND2_GND2") (pintype "bidirectional"))
      (node (ref "J1") (pin "P$1") (pinfunction "P$1_P$1") (pintype "bidirectional"))
      (node (ref "J3") (pin "P$2") (pinfunction "P$2_P$2") (pintype "bidirectional"))
      (node (ref "R13") (pin "1") (pinfunction "1_1") (pintype "passive"))
      (node (ref "R14") (pin "1") (pinfunction "1_1") (pintype "passive"))
      (node (ref "R16") (pin "1") (pinfunction "1_1") (pintype "passive"))
      (node (ref "R17") (pin "1") (pinfunction "1_1") (pintype "passive"))
      (node (ref "R18") (pin "1") (pinfunction "1_1") (pintype "passive"))
      (node (ref "R19") (pin "1") (pinfunction "1_1") (pintype "passive"))
      (node (ref "R20") (pin "1") (pinfunction "1_1") (pintype "passive"))
      (node (ref "R26") (pin "1") (pinfunction "1_1") (pintype "passive"))
      (node (ref "R3") (pin "2") (pinfunction "2_2") (pintype "passive"))
      (node (ref "R33") (pin "2") (pinfunction "2_2") (pintype "passive"))
      (node (ref "R37") (pin "2") (pinfunction "2_2") (pintype "passive"))
      (node (ref "R41") (pin "2") (pinfunction "2_2") (pintype "passive"))
      (node (ref "R45") (pin "2") (pinfunction "2_2") (pintype "passive"))
      (node (ref "R49") (pin "2") (pinfunction "2_2") (pintype "passive"))
      (node (ref "R53") (pin "2") (pinfunction "2_2") (pintype "passive"))
      (node (ref "SWD") (pin "5") (pinfunction "RST_5") (pintype "output"))
      (node (ref "U1") (pin "C") (pinfunction "C_C") (pintype "bidirectional"))
      (node (ref "U2") (pin "C") (pinfunction "C_C") (pintype "bidirectional"))
      (node (ref "U3") (pin "C") (pinfunction "C_C") (pintype "bidirectional"))
      (node (ref "U4") (pin "C") (pinfunction "C_C") (pintype "bidirectional"))
      (node (ref "U5") (pin "C") (pinfunction "C_C") (pintype "bidirectional"))
      (node (ref "U6") (pin "C") (pinfunction "C_C") (pintype "bidirectional"))
      (node (ref "U7") (pin "C") (pinfunction "C_C") (pintype "bidirectional"))
      (node (ref "X1") (pin "2") (pinfunction "G1_2") (pintype "bidirectional"))
      (node (ref "X1") (pin "4") (pinfunction "G2_4") (pintype "bidirectional"))
    )
    (net (code "40") (name "Net-(C1-Pad2)") (class "Default")
      (node (ref "C1") (pin "2") (pinfunction "2_2") (pintype "passive"))
      (node (ref "R1") (pin "2") (pinfunction "2_2") (pintype "passive"))
      (node (ref "U1") (pin "A") (pinfunction "A_A") (pintype "bidirectional"))
    )
    (net (code "41") (name "Net-(C15-Pad2)") (class "Default")
      (node (ref "C15") (pin "2") (pinfunction "2_2") (pintype "passive"))
      (node (ref "R31") (pin "2") (pinfunction "2_2") (pintype "passive"))
      (node (ref "U2") (pin "A") (pinfunction "A_A") (pintype "bidirectional"))
    )
    (net (code "42") (name "Net-(C16-Pad2)") (class "Default")
      (node (ref "C16") (pin "2") (pinfunction "2_2") (pintype "passive"))
      (node (ref "R35") (pin "2") (pinfunction "2_2") (pintype "passive"))
      (node (ref "U3") (pin "A") (pinfunction "A_A") (pintype "bidirectional"))
    )
    (net (code "43") (name "Net-(D1-PadA)") (class "Default")
      (node (ref "D1") (pin "A") (pinfunction "A_A") (pintype "passive"))
      (node (ref "R2") (pin "1") (pinfunction "1_1") (pintype "passive"))
    )
    (net (code "44") (name "Net-(D3-PadC)") (class "Default")
      (node (ref "D3") (pin "C") (pinfunction "C_C") (pintype "passive"))
      (node (ref "R17") (pin "2") (pinfunction "2_2") (pintype "passive"))
    )
    (net (code "45") (name "Net-(D4-PadC)") (class "Default")
      (node (ref "D4") (pin "C") (pinfunction "C_C") (pintype "passive"))
      (node (ref "R18") (pin "2") (pinfunction "2_2") (pintype "passive"))
    )
    (net (code "46") (name "Net-(D5-PadC)") (class "Default")
      (node (ref "D5") (pin "C") (pinfunction "C_C") (pintype "passive"))
      (node (ref "R19") (pin "2") (pinfunction "2_2") (pintype "passive"))
    )
    (net (code "47") (name "Net-(D9-PadA)") (class "Default")
      (node (ref "D9") (pin "A") (pinfunction "A_A") (pintype "passive"))
      (node (ref "R32") (pin "1") (pinfunction "1_1") (pintype "passive"))
    )
    (net (code "48") (name "Net-(D10-PadA)") (class "Default")
      (node (ref "D10") (pin "A") (pinfunction "A_A") (pintype "passive"))
      (node (ref "R36") (pin "1") (pinfunction "1_1") (pintype "passive"))
    )
    (net (code "49") (name "Net-(D11-PadA)") (class "Default")
      (node (ref "D11") (pin "A") (pinfunction "A_A") (pintype "passive"))
      (node (ref "R40") (pin "1") (pinfunction "1_1") (pintype "passive"))
    )
    (net (code "50") (name "Net-(D12-PadA)") (class "Default")
      (node (ref "D12") (pin "A") (pinfunction "A_A") (pintype "passive"))
      (node (ref "R44") (pin "1") (pinfunction "1_1") (pintype "passive"))
    )
    (net (code "51") (name "Net-(D13-PadA)") (class "Default")
      (node (ref "D13") (pin "A") (pinfunction "A_A") (pintype "passive"))
      (node (ref "R48") (pin "1") (pinfunction "1_1") (pintype "passive"))
    )
    (net (code "52") (name "Net-(D14-PadA)") (class "Default")
      (node (ref "D14") (pin "A") (pinfunction "A_A") (pintype "passive"))
      (node (ref "R52") (pin "1") (pinfunction "1_1") (pintype "passive"))
    )
    (net (code "53") (name "Net-(IC1-PadDIR)") (class "Default")
      (node (ref "IC1") (pin "DIR") (pinfunction "DIR_DIR") (pintype "bidirectional"))
      (node (ref "R12") (pin "2") (pinfunction "2_2") (pintype "passive"))
    )
    (net (code "54") (name "Net-(IC1-PadFAULT)") (class "Default")
      (node (ref "IC1") (pin "FAULT") (pinfunction "FAULT_FAULT") (pintype "bidirectional"))
      (node (ref "R10") (pin "1") (pinfunction "1_1") (pintype "passive"))
      (node (ref "R9") (pin "1") (pinfunction "1_1") (pintype "passive"))
    )
    (net (code "55") (name "Net-(IC1-PadRST)") (class "Default")
      (node (ref "IC1") (pin "RST") (pinfunction "RST_RST") (pintype "bidirectional"))
      (node (ref "IC1") (pin "SLEEP") (pinfunction "SLEEP_SLEEP") (pintype "bidirectional"))
      (node (ref "R15") (pin "2") (pinfunction "2_2") (pintype "passive"))
    )
    (net (code "56") (name "Net-(IC1-PadSTEP)") (class "Default")
      (node (ref "IC1") (pin "STEP") (pinfunction "STEP_STEP") (pintype "bidirectional"))
      (node (ref "R11") (pin "2") (pinfunction "2_2") (pintype "passive"))
    )
    (net (code "57") (name "Net-(R39-Pad2)") (class "Default")
      (node (ref "R39") (pin "2") (pinfunction "2_2") (pintype "passive"))
      (node (ref "U4") (pin "A") (pinfunction "A_A") (pintype "bidirectional"))
    )
    (net (code "58") (name "Net-(R43-Pad2)") (class "Default")
      (node (ref "R43") (pin "2") (pinfunction "2_2") (pintype "passive"))
      (node (ref "U5") (pin "A") (pinfunction "A_A") (pintype "bidirectional"))
    )
    (net (code "59") (name "Net-(R47-Pad2)") (class "Default")
      (node (ref "R47") (pin "2") (pinfunction "2_2") (pintype "passive"))
      (node (ref "U6") (pin "A") (pinfunction "A_A") (pintype "bidirectional"))
    )
    (net (code "60") (name "Net-(R51-Pad2)") (class "Default")
      (node (ref "R51") (pin "2") (pinfunction "2_2") (pintype "passive"))
      (node (ref "U7") (pin "A") (pinfunction "A_A") (pintype "bidirectional"))
    )
    (net (code "61") (name "Net-(U1-EMITTER)") (class "Default")
      (node (ref "R3") (pin "1") (pinfunction "1_1") (pintype "passive"))
      (node (ref "R4") (pin "1") (pinfunction "1_1") (pintype "passive"))
      (node (ref "U1") (pin "EMIT") (pinfunction "EMITTER_EMIT") (pintype "bidirectional"))
    )
    (net (code "62") (name "Net-(U2-EMITTER)") (class "Default")
      (node (ref "R33") (pin "1") (pinfunction "1_1") (pintype "passive"))
      (node (ref "R34") (pin "1") (pinfunction "1_1") (pintype "passive"))
      (node (ref "U2") (pin "EMIT") (pinfunction "EMITTER_EMIT") (pintype "bidirectional"))
    )
    (net (code "63") (name "Net-(U3-EMITTER)") (class "Default")
      (node (ref "R37") (pin "1") (pinfunction "1_1") (pintype "passive"))
      (node (ref "R38") (pin "1") (pinfunction "1_1") (pintype "passive"))
      (node (ref "U3") (pin "EMIT") (pinfunction "EMITTER_EMIT") (pintype "bidirectional"))
    )
    (net (code "64") (name "Net-(U4-EMITTER)") (class "Default")
      (node (ref "R41") (pin "1") (pinfunction "1_1") (pintype "passive"))
      (node (ref "R42") (pin "1") (pinfunction "1_1") (pintype "passive"))
      (node (ref "U4") (pin "EMIT") (pinfunction "EMITTER_EMIT") (pintype "bidirectional"))
    )
    (net (code "65") (name "Net-(U5-EMITTER)") (class "Default")
      (node (ref "R45") (pin "1") (pinfunction "1_1") (pintype "passive"))
      (node (ref "R46") (pin "1") (pinfunction "1_1") (pintype "passive"))
      (node (ref "U5") (pin "EMIT") (pinfunction "EMITTER_EMIT") (pintype "bidirectional"))
    )
    (net (code "66") (name "Net-(U6-EMITTER)") (class "Default")
      (node (ref "R49") (pin "1") (pinfunction "1_1") (pintype "passive"))
      (node (ref "R50") (pin "1") (pinfunction "1_1") (pintype "passive"))
      (node (ref "U6") (pin "EMIT") (pinfunction "EMITTER_EMIT") (pintype "bidirectional"))
    )
    (net (code "67") (name "Net-(U7-EMITTER)") (class "Default")
      (node (ref "R53") (pin "1") (pinfunction "1_1") (pintype "passive"))
      (node (ref "R54") (pin "1") (pinfunction "1_1") (pintype "passive"))
      (node (ref "U7") (pin "EMIT") (pinfunction "EMITTER_EMIT") (pintype "bidirectional"))
    )
    (net (code "68") (name "Net-(X1-P$1)") (class "Default")
      (node (ref "C12") (pin "2") (pinfunction "2_2") (pintype "passive"))
      (node (ref "IC3") (pin "2-OSC_IN") (pinfunction "2-OSC_IN_2-OSC_IN") (pintype "bidirectional"))
      (node (ref "X1") (pin "3") (pinfunction "P$1_3") (pintype "bidirectional"))
    )
    (net (code "69") (name "Net-(X1-P$2)") (class "Default")
      (node (ref "C13") (pin "2") (pinfunction "2_2") (pintype "passive"))
      (node (ref "IC3") (pin "3-OSC_OUT") (pinfunction "3-OSC_OUT_3-OSC_OUT") (pintype "bidirectional"))
      (node (ref "X1") (pin "1") (pinfunction "P$2_1") (pintype "bidirectional"))
    )
    (net (code "70") (name "unconnected-(IC1-EN-PadENABLE)") (class "Default")
      (node (ref "IC1") (pin "ENABLE") (pinfunction "EN_ENABLE") (pintype "bidirectional"))
    )
    (net (code "71") (name "unconnected-(IC1-PadM0)") (class "Default")
      (node (ref "IC1") (pin "M0") (pinfunction "M0_M0") (pintype "bidirectional"))
    )
    (net (code "72") (name "unconnected-(IC1-PadM1)") (class "Default")
      (node (ref "IC1") (pin "M1") (pinfunction "M1_M1") (pintype "bidirectional"))
    )
    (net (code "73") (name "unconnected-(IC1-PadM2)") (class "Default")
      (node (ref "IC1") (pin "M2") (pinfunction "M2_M2") (pintype "bidirectional"))
    )
    (net (code "74") (name "unconnected-(IC2-Pad7)") (class "Default")
      (node (ref "IC2") (pin "7") (pinfunction "7_7") (pintype "bidirectional"))
    )
    (net (code "75") (name "unconnected-(IC2-Pad8)") (class "Default")
      (node (ref "IC2") (pin "8") (pinfunction "8_8") (pintype "bidirectional"))
    )
    (net (code "76") (name "unconnected-(IC2-~{ON}{slash}OFF-Pad5)") (class "Default")
      (node (ref "IC2") (pin "5") (pinfunction "~{ON}/OFF_5") (pintype "bidirectional"))
    )
    (net (code "77") (name "unconnected-(IC3-Pad18-PA8)") (class "Default")
      (node (ref "IC3") (pin "18-PA8") (pinfunction "18-PA8_18-PA8") (pintype "bidirectional"))
    )
    (net (code "78") (name "unconnected-(IC3-Pad19-PA9)") (class "Default")
      (node (ref "IC3") (pin "19-PA9") (pinfunction "19-PA9_19-PA9") (pintype "bidirectional"))
    )
    (net (code "79") (name "unconnected-(IC3-Pad20-PA10)") (class "Default")
      (node (ref "IC3") (pin "20-PA10") (pinfunction "20-PA10_20-PA10") (pintype "bidirectional"))
    )
    (net (code "80") (name "unconnected-(IC3-Pad21-PA11)") (class "Default")
      (node (ref "IC3") (pin "21-PA11") (pinfunction "21-PA11_21-PA11") (pintype "bidirectional"))
    )
    (net (code "81") (name "unconnected-(J2-Pad8)") (class "Default")
      (node (ref "J2") (pin "8") (pinfunction "8_8") (pintype "bidirectional"))
    )
  )
)
